# 09_Ethernet-RGMII.net
KiCad netlist of a schematic drawn in Altium Designer
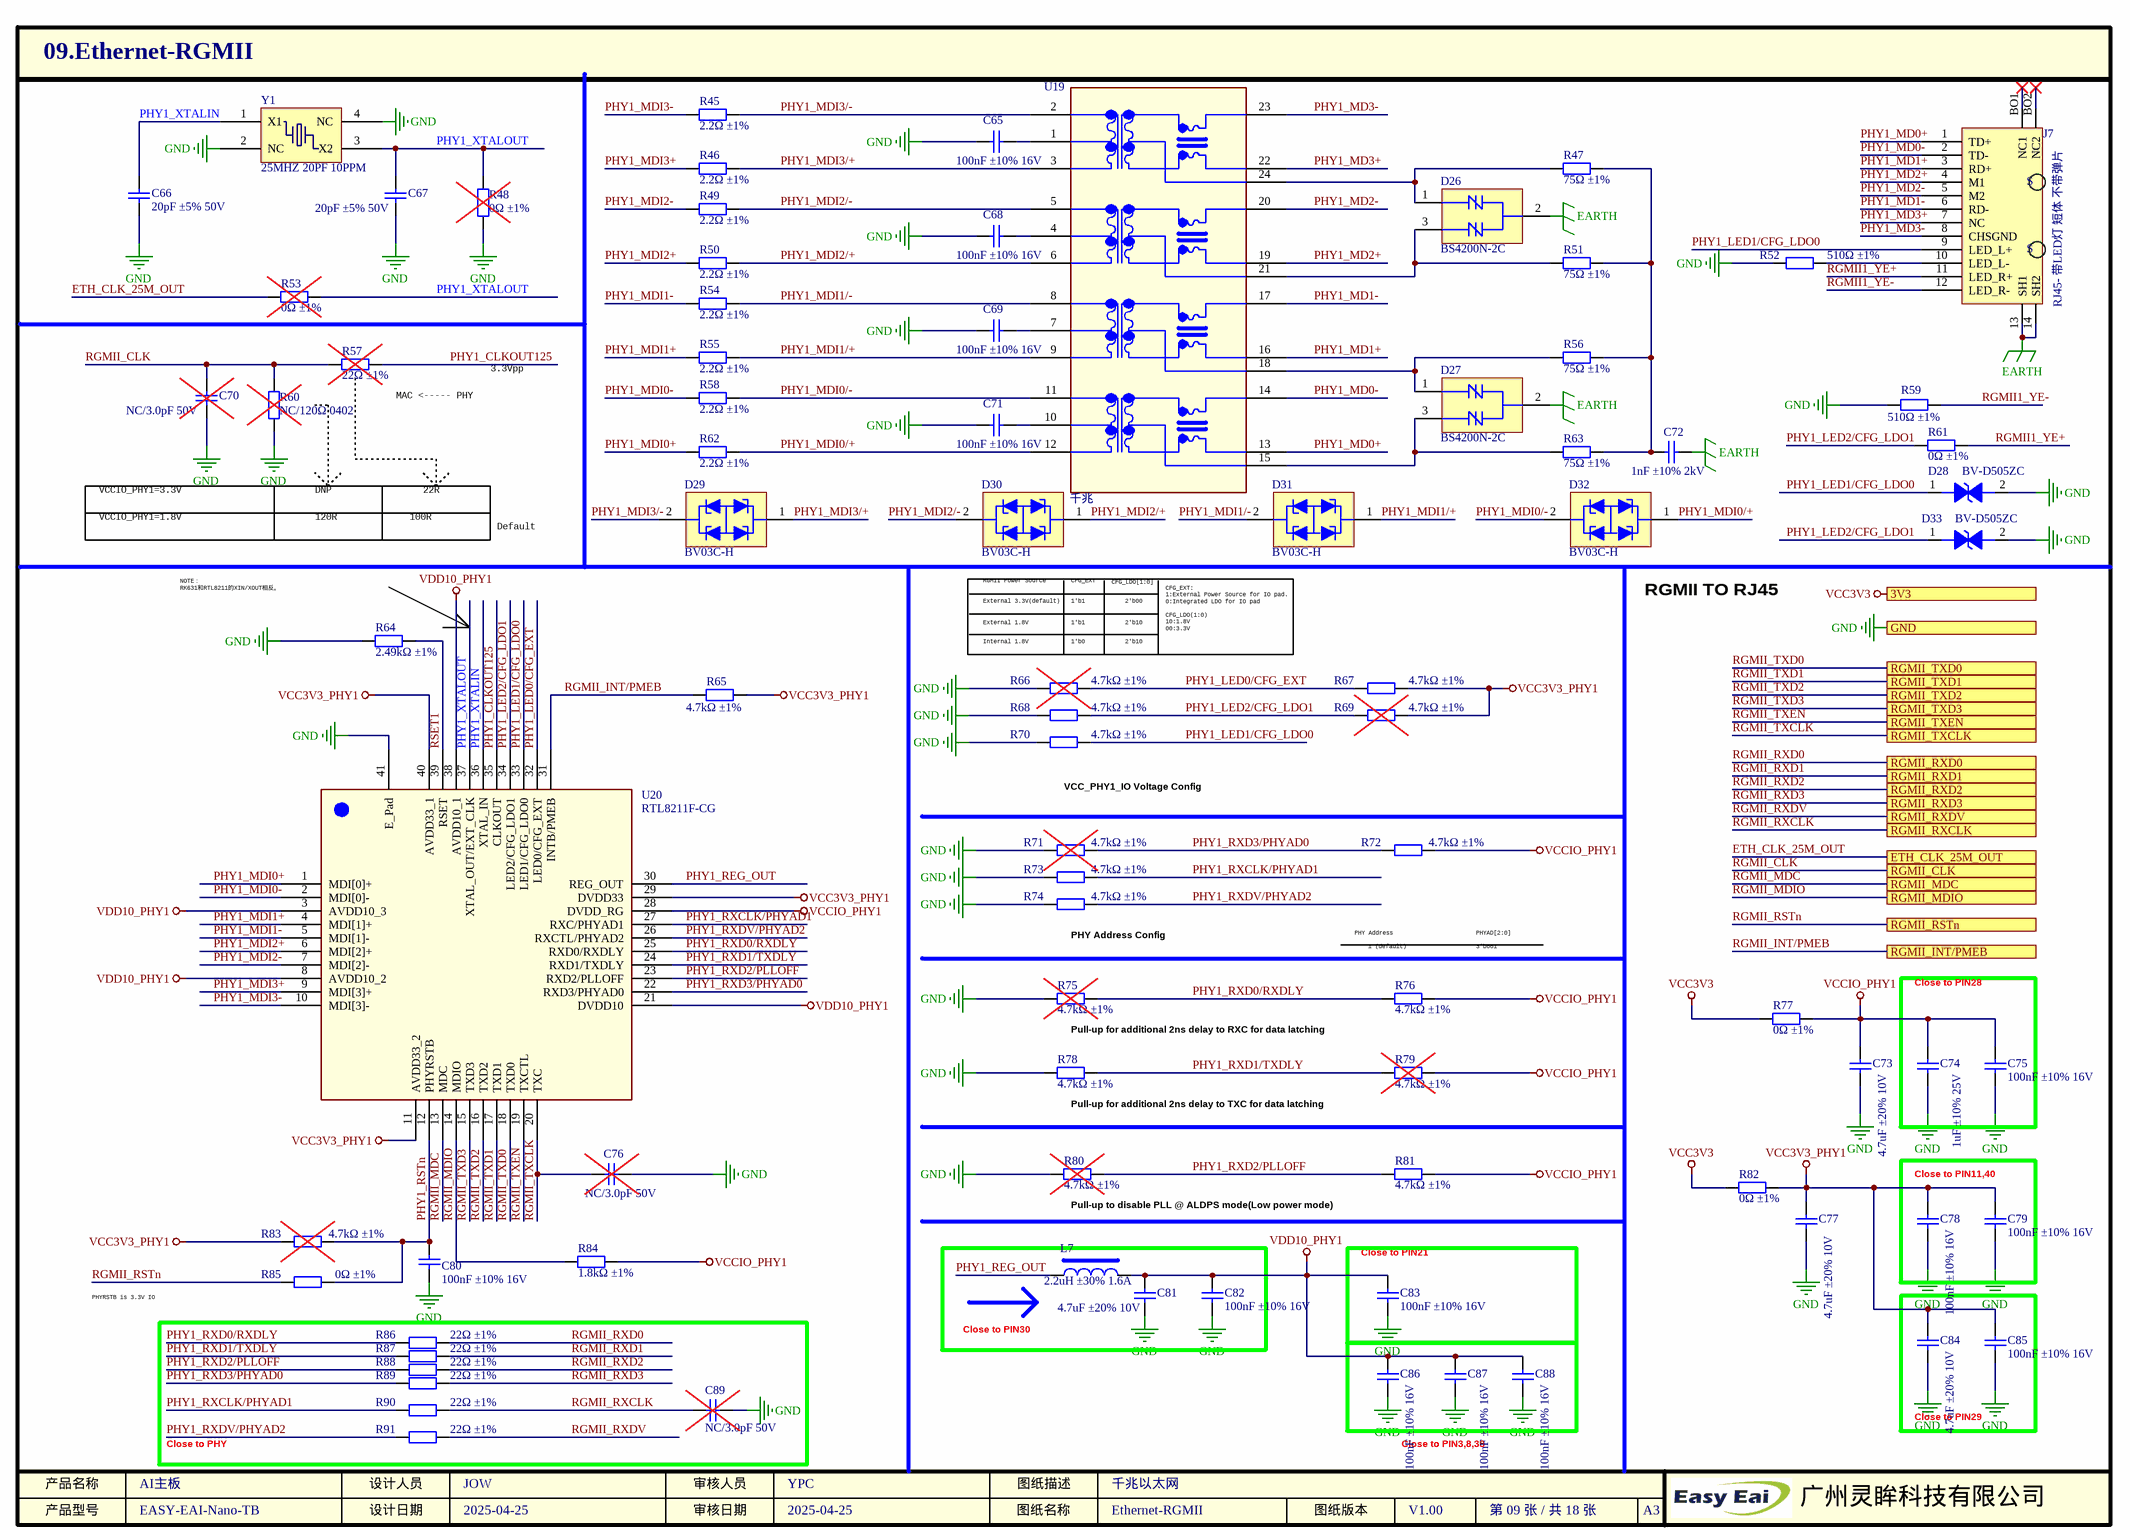
[diagram p0: 09.Ethernet-RGMII.SchDoc]

(export (version "E")
  (design (tool "Eeschema 10.0.6"))
  (components
    (comp (ref "C65")
      (value "CL05B104KO5NNNC")
      (footprint "0402_C")
      (description "SPZL000259")
      (fields (field (name "描述") "100nF ±10% 16V"))
      (libsource (lib "CAP_lexing") (part "0402 100nF ±10% 16V"))
    )
    (comp (ref "C66")
      (value "0402CG200J500NT")
      (footprint "0402_C")
      (description "SPZL000398")
      (fields (field (name "描述") "20pF ±5% 50V"))
      (libsource (lib "CAP_lexing") (part "0402 20pF ±5% 50V"))
    )
    (comp (ref "C67")
      (value "0402CG200J500NT")
      (footprint "0402_C")
      (description "SPZL000398")
      (fields (field (name "描述") "20pF ±5% 50V"))
      (libsource (lib "CAP_lexing") (part "0402 20pF ±5% 50V"))
    )
    (comp (ref "C68")
      (value "CL05B104KO5NNNC")
      (footprint "0402_C")
      (description "SPZL000259")
      (fields (field (name "描述") "100nF ±10% 16V"))
      (libsource (lib "CAP_lexing") (part "0402 100nF ±10% 16V"))
    )
    (comp (ref "C69")
      (value "CL05B104KO5NNNC")
      (footprint "0402_C")
      (description "SPZL000259")
      (fields (field (name "描述") "100nF ±10% 16V"))
      (libsource (lib "CAP_lexing") (part "0402 100nF ±10% 16V"))
    )
    (comp (ref "C70")
      (value "NC/3.0pF 50V")
      (footprint "0402_C")
      (description "贴片电容")
      (libsource (lib "Cap") (part "0402 2.0pF (2R0) 0.25pF 50V"))
    )
    (comp (ref "C71")
      (value "CL05B104KO5NNNC")
      (footprint "0402_C")
      (description "SPZL000259")
      (fields (field (name "描述") "100nF ±10% 16V"))
      (libsource (lib "CAP_lexing") (part "0402 100nF ±10% 16V"))
    )
    (comp (ref "C72")
      (value "CC1206KKX7RDBB102")
      (footprint "1206_C")
      (description "SPZL000332")
      (fields (field (name "描述") "1nF ±10% 2kV"))
      (libsource (lib "CAP_lexing") (part "1206 1nF ±10% 2kV"))
    )
    (comp (ref "C73")
      (value "CL05A475MP5NRNC")
      (footprint "0402_C")
      (description "SPZL000339")
      (fields (field (name "描述") "4.7uF ±20% 10V"))
      (libsource (lib "CAP_lexing") (part "0402 4.7uF ±20% 10V"))
    )
    (comp (ref "C74")
      (value "CL05A105KA5NQNC")
      (footprint "0402_C")
      (description "SPZL000337")
      (fields (field (name "描述") "1uF ±10% 25V"))
      (libsource (lib "CAP_lexing") (part "0402 1uF ±10% 25V"))
    )
    (comp (ref "C75")
      (value "CL05B104KO5NNNC")
      (footprint "0402_C")
      (description "SPZL000259")
      (fields (field (name "描述") "100nF ±10% 16V"))
      (libsource (lib "CAP_lexing") (part "0402 100nF ±10% 16V"))
    )
    (comp (ref "C76")
      (value "NC/3.0pF 50V")
      (footprint "0402_C")
      (description "贴片电容")
      (libsource (lib "Cap") (part "0402 2.0pF (2R0) 0.25pF 50V"))
    )
    (comp (ref "C77")
      (value "CL05A475MP5NRNC")
      (footprint "0402_C")
      (description "SPZL000339")
      (fields (field (name "描述") "4.7uF ±20% 10V"))
      (libsource (lib "CAP_lexing") (part "0402 4.7uF ±20% 10V"))
    )
    (comp (ref "C78")
      (value "CL05B104KO5NNNC")
      (footprint "0402_C")
      (description "SPZL000259")
      (fields (field (name "描述") "100nF ±10% 16V"))
      (libsource (lib "CAP_lexing") (part "0402 100nF ±10% 16V"))
    )
    (comp (ref "C79")
      (value "CL05B104KO5NNNC")
      (footprint "0402_C")
      (description "SPZL000259")
      (fields (field (name "描述") "100nF ±10% 16V"))
      (libsource (lib "CAP_lexing") (part "0402 100nF ±10% 16V"))
    )
    (comp (ref "C80")
      (value "CL05B104KO5NNNC")
      (footprint "0402_C")
      (description "SPZL000259")
      (fields (field (name "描述") "100nF ±10% 16V"))
      (libsource (lib "CAP_lexing") (part "0402 100nF ±10% 16V"))
    )
    (comp (ref "C81")
      (value "CL05A475MP5NRNC")
      (footprint "0402_C")
      (description "SPZL000339")
      (fields (field (name "描述") "4.7uF ±20% 10V"))
      (libsource (lib "CAP_lexing") (part "0402 4.7uF ±20% 10V"))
    )
    (comp (ref "C82")
      (value "CL05B104KO5NNNC")
      (footprint "0402_C")
      (description "SPZL000259")
      (fields (field (name "描述") "100nF ±10% 16V"))
      (libsource (lib "CAP_lexing") (part "0402 100nF ±10% 16V"))
    )
    (comp (ref "C83")
      (value "CL05B104KO5NNNC")
      (footprint "0402_C")
      (description "SPZL000259")
      (fields (field (name "描述") "100nF ±10% 16V"))
      (libsource (lib "CAP_lexing") (part "0402 100nF ±10% 16V"))
    )
    (comp (ref "C84")
      (value "CL05A475MP5NRNC")
      (footprint "0402_C")
      (description "SPZL000339")
      (fields (field (name "描述") "4.7uF ±20% 10V"))
      (libsource (lib "CAP_lexing") (part "0402 4.7uF ±20% 10V"))
    )
    (comp (ref "C85")
      (value "CL05B104KO5NNNC")
      (footprint "0402_C")
      (description "SPZL000259")
      (fields (field (name "描述") "100nF ±10% 16V"))
      (libsource (lib "CAP_lexing") (part "0402 100nF ±10% 16V"))
    )
    (comp (ref "C86")
      (value "CL05B104KO5NNNC")
      (footprint "0402_C")
      (description "SPZL000259")
      (fields (field (name "描述") "100nF ±10% 16V"))
      (libsource (lib "CAP_lexing") (part "0402 100nF ±10% 16V"))
    )
    (comp (ref "C87")
      (value "CL05B104KO5NNNC")
      (footprint "0402_C")
      (description "SPZL000259")
      (fields (field (name "描述") "100nF ±10% 16V"))
      (libsource (lib "CAP_lexing") (part "0402 100nF ±10% 16V"))
    )
    (comp (ref "C88")
      (value "CL05B104KO5NNNC")
      (footprint "0402_C")
      (description "SPZL000259")
      (fields (field (name "描述") "100nF ±10% 16V"))
      (libsource (lib "CAP_lexing") (part "0402 100nF ±10% 16V"))
    )
    (comp (ref "C89")
      (value "NC/3.0pF 50V")
      (footprint "0402_C")
      (description "贴片电容")
      (libsource (lib "Cap") (part "0402 2.0pF (2R0) 0.25pF 50V"))
    )
    (comp (ref "D26")
      (value "BS4200N-2C")
      (footprint "SMB-T_L5.4-W3.3-BI")
      (description "SPZL000612")
      (fields (field (name "型号") "BS4200N-2C"))
      (libsource (lib "ESD_lexing") (part "放电管 BS4200N-2C"))
    )
    (comp (ref "D27")
      (value "BS4200N-2C")
      (footprint "SMB-T_L5.4-W3.3-BI")
      (description "SPZL000612")
      (fields (field (name "型号") "BS4200N-2C"))
      (libsource (lib "ESD_lexing") (part "放电管 BS4200N-2C"))
    )
    (comp (ref "D28")
      (value "BV-D505ZC")
      (footprint "SOD-523")
      (description "SPZL000613")
      (fields (field (name "型号") "BV-D505ZC"))
      (libsource (lib "ESD_lexing") (part "ESD BV-D505ZC"))
    )
    (comp (ref "D29")
      (value "BV03C-H")
      (footprint "SOD-323")
      (description "SPZL000614")
      (fields (field (name "型号") "BV03C-H"))
      (libsource (lib "ESD_lexing") (part "ESD BV03C-H"))
    )
    (comp (ref "D30")
      (value "BV03C-H")
      (footprint "SOD-323")
      (description "SPZL000614")
      (fields (field (name "型号") "BV03C-H"))
      (libsource (lib "ESD_lexing") (part "ESD BV03C-H"))
    )
    (comp (ref "D31")
      (value "BV03C-H")
      (footprint "SOD-323")
      (description "SPZL000614")
      (fields (field (name "型号") "BV03C-H"))
      (libsource (lib "ESD_lexing") (part "ESD BV03C-H"))
    )
    (comp (ref "D32")
      (value "BV03C-H")
      (footprint "SOD-323")
      (description "SPZL000614")
      (fields (field (name "型号") "BV03C-H"))
      (libsource (lib "ESD_lexing") (part "ESD BV03C-H"))
    )
    (comp (ref "D33")
      (value "BV-D505ZC")
      (footprint "SOD-523")
      (description "SPZL000613")
      (fields (field (name "型号") "BV-D505ZC"))
      (libsource (lib "ESD_lexing") (part "ESD BV-D505ZC"))
    )
    (comp (ref "J7")
      (value "R-RJ45R08P-C000")
      (footprint "RJ45/LED-1575X1626X1310")
      (description "SPZL000140")
      (fields (field (name "描述") "RJ45- 带LED灯 短体 不带弹片"))
      (libsource (lib "EVBoard-RK3562") (part "RJ45- 带LED灯 短体 不带弹片"))
    )
    (comp (ref "L7")
      (value "SWPA3015S2R2NT")
      (footprint "IND-SMD_L3.0-W3.0")
      (description "SPZL000721")
      (fields (field (name "描述") "2.2uH ±30% 1.6A"))
      (libsource (lib "Inductor_lexing") (part "2.2uH ±30% 1.6A"))
    )
    (comp (ref "R45")
      (value "0402WGF220KTCE")
      (footprint "0402_R")
      (description "SPZL000327")
      (fields (field (name "描述") "2.2Ω ±1%"))
      (libsource (lib "RES_lexing") (part "0402 2.2Ω ±1%"))
    )
    (comp (ref "R46")
      (value "0402WGF220KTCE")
      (footprint "0402_R")
      (description "SPZL000327")
      (fields (field (name "描述") "2.2Ω ±1%"))
      (libsource (lib "RES_lexing") (part "0402 2.2Ω ±1%"))
    )
    (comp (ref "R47")
      (value "RS-05K75R0FT")
      (footprint "0805_R")
      (description "SPZL000353")
      (fields (field (name "描述") "75Ω ±1%"))
      (libsource (lib "RES_lexing") (part "0805 75Ω ±1%"))
    )
    (comp (ref "R48")
      (value "NC/0402WGF0000TCE")
      (footprint "0402_R")
      (description "SPZL000276")
      (fields (field (name "描述") "0Ω ±1%"))
      (libsource (lib "RES_lexing") (part "0402 0Ω ±1%"))
    )
    (comp (ref "R49")
      (value "0402WGF220KTCE")
      (footprint "0402_R")
      (description "SPZL000327")
      (fields (field (name "描述") "2.2Ω ±1%"))
      (libsource (lib "RES_lexing") (part "0402 2.2Ω ±1%"))
    )
    (comp (ref "R50")
      (value "0402WGF220KTCE")
      (footprint "0402_R")
      (description "SPZL000327")
      (fields (field (name "描述") "2.2Ω ±1%"))
      (libsource (lib "RES_lexing") (part "0402 2.2Ω ±1%"))
    )
    (comp (ref "R51")
      (value "RS-05K75R0FT")
      (footprint "0805_R")
      (description "SPZL000353")
      (fields (field (name "描述") "75Ω ±1%"))
      (libsource (lib "RES_lexing") (part "0805 75Ω ±1%"))
    )
    (comp (ref "R52")
      (value "0402WGF5100TCE")
      (footprint "0402_R")
      (description "SPZL000335")
      (fields (field (name "描述") "510Ω ±1%"))
      (libsource (lib "RES_lexing") (part "0402 510Ω ±1%"))
    )
    (comp (ref "R53")
      (value "NC/0402WGF0000TCE")
      (footprint "0402_R")
      (description "SPZL000276")
      (fields (field (name "描述") "0Ω ±1%"))
      (libsource (lib "") (part "0402 0Ω ±1%_2"))
    )
    (comp (ref "R54")
      (value "0402WGF220KTCE")
      (footprint "0402_R")
      (description "SPZL000327")
      (fields (field (name "描述") "2.2Ω ±1%"))
      (libsource (lib "RES_lexing") (part "0402 2.2Ω ±1%"))
    )
    (comp (ref "R55")
      (value "0402WGF220KTCE")
      (footprint "0402_R")
      (description "SPZL000327")
      (fields (field (name "描述") "2.2Ω ±1%"))
      (libsource (lib "RES_lexing") (part "0402 2.2Ω ±1%"))
    )
    (comp (ref "R56")
      (value "RS-05K75R0FT")
      (footprint "0805_R")
      (description "SPZL000353")
      (fields (field (name "描述") "75Ω ±1%"))
      (libsource (lib "RES_lexing") (part "0805 75Ω ±1%"))
    )
    (comp (ref "R57")
      (value "0402WGF220JTCE")
      (footprint "0402_R")
      (description "SPZL000279")
      (fields (field (name "描述") "22Ω ±1%"))
      (libsource (lib "RES_lexing") (part "0402 22Ω ±1%"))
    )
    (comp (ref "R58")
      (value "0402WGF220KTCE")
      (footprint "0402_R")
      (description "SPZL000327")
      (fields (field (name "描述") "2.2Ω ±1%"))
      (libsource (lib "RES_lexing") (part "0402 2.2Ω ±1%"))
    )
    (comp (ref "R59")
      (value "0402WGF5100TCE")
      (footprint "0402_R")
      (description "SPZL000335")
      (fields (field (name "描述") "510Ω ±1%"))
      (libsource (lib "RES_lexing") (part "0402 510Ω ±1%"))
    )
    (comp (ref "R60")
      (value "NC/120Ω 0402")
      (footprint "0402_R")
      (description "贴片电阻")
      (libsource (lib "RES") (part "0402 120Ω (1200) 1%"))
    )
    (comp (ref "R61")
      (value "0402WGF0000TCE")
      (footprint "0402_R")
      (description "SPZL000276")
      (fields (field (name "描述") "0Ω ±1%"))
      (libsource (lib "") (part "0402 0Ω ±1%_1"))
    )
    (comp (ref "R62")
      (value "0402WGF220KTCE")
      (footprint "0402_R")
      (description "SPZL000327")
      (fields (field (name "描述") "2.2Ω ±1%"))
      (libsource (lib "RES_lexing") (part "0402 2.2Ω ±1%"))
    )
    (comp (ref "R63")
      (value "RS-05K75R0FT")
      (footprint "0805_R")
      (description "SPZL000353")
      (fields (field (name "描述") "75Ω ±1%"))
      (libsource (lib "RES_lexing") (part "0805 75Ω ±1%"))
    )
    (comp (ref "R64")
      (value "AC0402FR-072K49L")
      (footprint "0402_R")
      (description "SPZL000354")
      (fields (field (name "描述") "2.49kΩ ±1%"))
      (libsource (lib "RES_lexing") (part "0402 2.49kΩ ±1%"))
    )
    (comp (ref "R65")
      (value "0402WGF4701TCE")
      (footprint "0402_R")
      (description "SPZL000280")
      (fields (field (name "描述") "4.7kΩ ±1%"))
      (libsource (lib "RES_lexing") (part "0402 4.7kΩ ±1%"))
    )
    (comp (ref "R66")
      (value "NC/0402WGF4701TCE")
      (footprint "0402_R")
      (description "SPZL000280")
      (fields (field (name "描述") "4.7kΩ ±1%"))
      (libsource (lib "RES_lexing") (part "0402 4.7kΩ ±1%"))
    )
    (comp (ref "R67")
      (value "0402WGF4701TCE")
      (footprint "0402_R")
      (description "SPZL000280")
      (fields (field (name "描述") "4.7kΩ ±1%"))
      (libsource (lib "RES_lexing") (part "0402 4.7kΩ ±1%"))
    )
    (comp (ref "R68")
      (value "0402WGF4701TCE")
      (footprint "0402_R")
      (description "SPZL000280")
      (fields (field (name "描述") "4.7kΩ ±1%"))
      (libsource (lib "RES_lexing") (part "0402 4.7kΩ ±1%"))
    )
    (comp (ref "R69")
      (value "NC/0402WGF4701TCE")
      (footprint "0402_R")
      (description "SPZL000280")
      (fields (field (name "描述") "4.7kΩ ±1%"))
      (libsource (lib "RES_lexing") (part "0402 4.7kΩ ±1%"))
    )
    (comp (ref "R70")
      (value "0402WGF4701TCE")
      (footprint "0402_R")
      (description "SPZL000280")
      (fields (field (name "描述") "4.7kΩ ±1%"))
      (libsource (lib "RES_lexing") (part "0402 4.7kΩ ±1%"))
    )
    (comp (ref "R71")
      (value "NC/0402WGF4701TCE")
      (footprint "0402_R")
      (description "SPZL000280")
      (fields (field (name "描述") "4.7kΩ ±1%"))
      (libsource (lib "RES_lexing") (part "0402 4.7kΩ ±1%"))
    )
    (comp (ref "R72")
      (value "0402WGF4701TCE")
      (footprint "0402_R")
      (description "SPZL000280")
      (fields (field (name "描述") "4.7kΩ ±1%"))
      (libsource (lib "RES_lexing") (part "0402 4.7kΩ ±1%"))
    )
    (comp (ref "R73")
      (value "0402WGF4701TCE")
      (footprint "0402_R")
      (description "SPZL000280")
      (fields (field (name "描述") "4.7kΩ ±1%"))
      (libsource (lib "RES_lexing") (part "0402 4.7kΩ ±1%"))
    )
    (comp (ref "R74")
      (value "0402WGF4701TCE")
      (footprint "0402_R")
      (description "SPZL000280")
      (fields (field (name "描述") "4.7kΩ ±1%"))
      (libsource (lib "RES_lexing") (part "0402 4.7kΩ ±1%"))
    )
    (comp (ref "R75")
      (value "NC/0402WGF4701TCE")
      (footprint "0402_R")
      (description "SPZL000280")
      (fields (field (name "描述") "4.7kΩ ±1%"))
      (libsource (lib "RES_lexing") (part "0402 4.7kΩ ±1%"))
    )
    (comp (ref "R76")
      (value "0402WGF4701TCE")
      (footprint "0402_R")
      (description "SPZL000280")
      (fields (field (name "描述") "4.7kΩ ±1%"))
      (libsource (lib "RES_lexing") (part "0402 4.7kΩ ±1%"))
    )
    (comp (ref "R77")
      (value "0402WGF0000TCE")
      (footprint "0402_R")
      (description "SPZL000276")
      (fields (field (name "描述") "0Ω ±1%"))
      (libsource (lib "") (part "0402 0Ω ±1%_1"))
    )
    (comp (ref "R78")
      (value "0402WGF4701TCE")
      (footprint "0402_R")
      (description "SPZL000280")
      (fields (field (name "描述") "4.7kΩ ±1%"))
      (libsource (lib "RES_lexing") (part "0402 4.7kΩ ±1%"))
    )
    (comp (ref "R79")
      (value "NC/0402WGF4701TCE")
      (footprint "0402_R")
      (description "SPZL000280")
      (fields (field (name "描述") "4.7kΩ ±1%"))
      (libsource (lib "RES_lexing") (part "0402 4.7kΩ ±1%"))
    )
    (comp (ref "R80")
      (value "NC/0402WGF4701TCE")
      (footprint "0402_R")
      (description "SPZL000280")
      (fields (field (name "描述") "4.7kΩ ±1%"))
      (libsource (lib "RES_lexing") (part "0402 4.7kΩ ±1%"))
    )
    (comp (ref "R81")
      (value "0402WGF4701TCE")
      (footprint "0402_R")
      (description "SPZL000280")
      (fields (field (name "描述") "4.7kΩ ±1%"))
      (libsource (lib "RES_lexing") (part "0402 4.7kΩ ±1%"))
    )
    (comp (ref "R82")
      (value "0402WGF0000TCE")
      (footprint "0402_R")
      (description "SPZL000276")
      (fields (field (name "描述") "0Ω ±1%"))
      (libsource (lib "") (part "0402 0Ω ±1%_1"))
    )
    (comp (ref "R83")
      (value "NC/0402WGF4701TCE")
      (footprint "0402_R")
      (description "SPZL000280")
      (fields (field (name "描述") "4.7kΩ ±1%"))
      (libsource (lib "RES_lexing") (part "0402 4.7kΩ ±1%"))
    )
    (comp (ref "R84")
      (value "0402WGF1801TCE")
      (footprint "0402_R")
      (description "SPZL000899")
      (fields (field (name "描述") "1.8kΩ ±1%"))
      (libsource (lib "RES_lexing") (part "0402 1.8kΩ ±1%"))
    )
    (comp (ref "R85")
      (value "0402WGF0000TCE")
      (footprint "0402_R")
      (description "SPZL000276")
      (fields (field (name "描述") "0Ω ±1%"))
      (libsource (lib "") (part "0402 0Ω ±1%_1"))
    )
    (comp (ref "R86")
      (value "0402WGF220JTCE")
      (footprint "0402_R")
      (description "SPZL000279")
      (fields (field (name "描述") "22Ω ±1%"))
      (libsource (lib "RES_lexing") (part "0402 22Ω ±1%"))
    )
    (comp (ref "R87")
      (value "0402WGF220JTCE")
      (footprint "0402_R")
      (description "SPZL000279")
      (fields (field (name "描述") "22Ω ±1%"))
      (libsource (lib "RES_lexing") (part "0402 22Ω ±1%"))
    )
    (comp (ref "R88")
      (value "0402WGF220JTCE")
      (footprint "0402_R")
      (description "SPZL000279")
      (fields (field (name "描述") "22Ω ±1%"))
      (libsource (lib "RES_lexing") (part "0402 22Ω ±1%"))
    )
    (comp (ref "R89")
      (value "0402WGF220JTCE")
      (footprint "0402_R")
      (description "SPZL000279")
      (fields (field (name "描述") "22Ω ±1%"))
      (libsource (lib "RES_lexing") (part "0402 22Ω ±1%"))
    )
    (comp (ref "R90")
      (value "0402WGF220JTCE")
      (footprint "0402_R")
      (description "SPZL000279")
      (fields (field (name "描述") "22Ω ±1%"))
      (libsource (lib "RES_lexing") (part "0402 22Ω ±1%"))
    )
    (comp (ref "R91")
      (value "0402WGF220JTCE")
      (footprint "0402_R")
      (description "SPZL000279")
      (fields (field (name "描述") "22Ω ±1%"))
      (libsource (lib "RES_lexing") (part "0402 22Ω ±1%"))
    )
    (comp (ref "U19")
      (value "G2401CE")
      (footprint "SMD-24_L15.1-W7.1-P1.00-LS10.0-BL")
      (description "SPZL000720")
      (fields (field (name "描述") "千兆"))
      (libsource (lib "ESD_lexing") (part "网络变压器 G2401CE"))
    )
    (comp (ref "U20")
      (value "RTL8211F-CG")
      (footprint "QFN40P500X500X90_HS-41N")
      (description "SPZL000719")
      (fields (field (name "型号") "RTL8211F-CG"))
      (libsource (lib "IC_lexing") (part "RTL8211F-CG"))
    )
    (comp (ref "Y1")
      (value "X322525MSB4SI")
      (footprint "SMD-3225_4P")
      (description "SPZL000475")
      (fields (field (name "描述") "25MHZ 20PF 10PPM"))
      (libsource (lib "XTAL_lexing") (part "25MHZ 20PF 10PPM"))
    )
  )
  (nets
    (net (code "1") (name "/ETH_CLK_25M_OUT") (class "Default")
      (node (ref "R53") (pin "2") (pinfunction "2_2") (pintype "passive"))
    )
    (net (code "2") (name "/PHY1_CLKOUT125") (class "Default")
      (node (ref "R57") (pin "2") (pinfunction "2_2") (pintype "passive"))
      (node (ref "U20") (pin "35") (pinfunction "CLKOUT_35") (pintype "passive"))
    )
    (net (code "3") (name "/PHY1_LED0{slash}CFG_EXT") (class "Default")
      (node (ref "R66") (pin "2") (pinfunction "2_2") (pintype "passive"))
      (node (ref "R67") (pin "1") (pinfunction "1_1") (pintype "passive"))
      (node (ref "U20") (pin "32") (pinfunction "LED0/CFG_EXT_32") (pintype "passive"))
    )
    (net (code "4") (name "/PHY1_LED1{slash}CFG_LDO0") (class "Default")
      (node (ref "D28") (pin "1") (pinfunction "1_1") (pintype "passive"))
      (node (ref "J7") (pin "9") (pinfunction "LED_L+_9") (pintype "passive"))
      (node (ref "R70") (pin "2") (pinfunction "2_2") (pintype "passive"))
      (node (ref "U20") (pin "33") (pinfunction "LED1/CFG_LDO0_33") (pintype "passive"))
    )
    (net (code "5") (name "/PHY1_LED2{slash}CFG_LDO1") (class "Default")
      (node (ref "D33") (pin "1") (pinfunction "1_1") (pintype "passive"))
      (node (ref "R61") (pin "1") (pinfunction "1_1") (pintype "passive"))
      (node (ref "R68") (pin "2") (pinfunction "2_2") (pintype "passive"))
      (node (ref "R69") (pin "1") (pinfunction "1_1") (pintype "passive"))
      (node (ref "U20") (pin "34") (pinfunction "LED2/CFG_LDO1_34") (pintype "passive"))
    )
    (net (code "6") (name "/PHY1_MD0+") (class "Default")
      (node (ref "J7") (pin "1") (pinfunction "TD+_1") (pintype "passive"))
      (node (ref "U19") (pin "13") (pinfunction "13_13") (pintype "passive"))
    )
    (net (code "7") (name "/PHY1_MD0-") (class "Default")
      (node (ref "J7") (pin "2") (pinfunction "TD-_2") (pintype "passive"))
      (node (ref "U19") (pin "14") (pinfunction "14_14") (pintype "passive"))
    )
    (net (code "8") (name "/PHY1_MD1+") (class "Default")
      (node (ref "J7") (pin "3") (pinfunction "RD+_3") (pintype "passive"))
      (node (ref "U19") (pin "16") (pinfunction "16_16") (pintype "passive"))
    )
    (net (code "9") (name "/PHY1_MD1-") (class "Default")
      (node (ref "J7") (pin "6") (pinfunction "RD-_6") (pintype "passive"))
      (node (ref "U19") (pin "17") (pinfunction "17_17") (pintype "passive"))
    )
    (net (code "10") (name "/PHY1_MD2+") (class "Default")
      (node (ref "J7") (pin "4") (pinfunction "M1_4") (pintype "passive"))
      (node (ref "U19") (pin "19") (pinfunction "19_19") (pintype "passive"))
    )
    (net (code "11") (name "/PHY1_MD2-") (class "Default")
      (node (ref "J7") (pin "5") (pinfunction "M2_5") (pintype "passive"))
      (node (ref "U19") (pin "20") (pinfunction "20_20") (pintype "passive"))
    )
    (net (code "12") (name "/PHY1_MD3+") (class "Default")
      (node (ref "J7") (pin "7") (pinfunction "NC_7") (pintype "passive"))
      (node (ref "U19") (pin "22") (pinfunction "22_22") (pintype "passive"))
    )
    (net (code "13") (name "/PHY1_MD3-") (class "Default")
      (node (ref "J7") (pin "8") (pinfunction "CHSGND_8") (pintype "passive"))
      (node (ref "U19") (pin "23") (pinfunction "23_23") (pintype "passive"))
    )
    (net (code "14") (name "/PHY1_MDI0+") (class "Default")
      (node (ref "R62") (pin "1") (pinfunction "1_1") (pintype "passive"))
      (node (ref "U20") (pin "1") (pinfunction "MDI[0]+_1") (pintype "passive"))
    )
    (net (code "15") (name "/PHY1_MDI0-") (class "Default")
      (node (ref "R58") (pin "1") (pinfunction "1_1") (pintype "passive"))
      (node (ref "U20") (pin "2") (pinfunction "MDI[0]-_2") (pintype "passive"))
    )
    (net (code "16") (name "/PHY1_MDI0{slash}+") (class "Default")
      (node (ref "D32") (pin "1") (pintype "passive"))
      (node (ref "R62") (pin "2") (pinfunction "2_2") (pintype "passive"))
      (node (ref "U19") (pin "12") (pinfunction "12_12") (pintype "passive"))
    )
    (net (code "17") (name "/PHY1_MDI0{slash}-") (class "Default")
      (node (ref "D32") (pin "2") (pintype "passive"))
      (node (ref "R58") (pin "2") (pinfunction "2_2") (pintype "passive"))
      (node (ref "U19") (pin "11") (pinfunction "11_11") (pintype "passive"))
    )
    (net (code "18") (name "/PHY1_MDI1+") (class "Default")
      (node (ref "R55") (pin "1") (pinfunction "1_1") (pintype "passive"))
      (node (ref "U20") (pin "4") (pinfunction "MDI[1]+_4") (pintype "passive"))
    )
    (net (code "19") (name "/PHY1_MDI1-") (class "Default")
      (node (ref "R54") (pin "1") (pinfunction "1_1") (pintype "passive"))
      (node (ref "U20") (pin "5") (pinfunction "MDI[1]-_5") (pintype "passive"))
    )
    (net (code "20") (name "/PHY1_MDI1{slash}+") (class "Default")
      (node (ref "D31") (pin "1") (pintype "passive"))
      (node (ref "R55") (pin "2") (pinfunction "2_2") (pintype "passive"))
      (node (ref "U19") (pin "9") (pinfunction "9_9") (pintype "passive"))
    )
    (net (code "21") (name "/PHY1_MDI1{slash}-") (class "Default")
      (node (ref "D31") (pin "2") (pintype "passive"))
      (node (ref "R54") (pin "2") (pinfunction "2_2") (pintype "passive"))
      (node (ref "U19") (pin "8") (pinfunction "8_8") (pintype "passive"))
    )
    (net (code "22") (name "/PHY1_MDI2+") (class "Default")
      (node (ref "R50") (pin "1") (pinfunction "1_1") (pintype "passive"))
      (node (ref "U20") (pin "6") (pinfunction "MDI[2]+_6") (pintype "passive"))
    )
    (net (code "23") (name "/PHY1_MDI2-") (class "Default")
      (node (ref "R49") (pin "1") (pinfunction "1_1") (pintype "passive"))
      (node (ref "U20") (pin "7") (pinfunction "MDI[2]-_7") (pintype "passive"))
    )
    (net (code "24") (name "/PHY1_MDI2{slash}+") (class "Default")
      (node (ref "D30") (pin "1") (pintype "passive"))
      (node (ref "R50") (pin "2") (pinfunction "2_2") (pintype "passive"))
      (node (ref "U19") (pin "6") (pinfunction "6_6") (pintype "passive"))
    )
    (net (code "25") (name "/PHY1_MDI2{slash}-") (class "Default")
      (node (ref "D30") (pin "2") (pintype "passive"))
      (node (ref "R49") (pin "2") (pinfunction "2_2") (pintype "passive"))
      (node (ref "U19") (pin "5") (pinfunction "5_5") (pintype "passive"))
    )
    (net (code "26") (name "/PHY1_MDI3+") (class "Default")
      (node (ref "R46") (pin "1") (pinfunction "1_1") (pintype "passive"))
      (node (ref "U20") (pin "9") (pinfunction "MDI[3]+_9") (pintype "passive"))
    )
    (net (code "27") (name "/PHY1_MDI3-") (class "Default")
      (node (ref "R45") (pin "1") (pinfunction "1_1") (pintype "passive"))
      (node (ref "U20") (pin "10") (pinfunction "MDI[3]-_10") (pintype "passive"))
    )
    (net (code "28") (name "/PHY1_MDI3{slash}+") (class "Default")
      (node (ref "D29") (pin "1") (pintype "passive"))
      (node (ref "R46") (pin "2") (pinfunction "2_2") (pintype "passive"))
      (node (ref "U19") (pin "3") (pinfunction "3_3") (pintype "passive"))
    )
    (net (code "29") (name "/PHY1_MDI3{slash}-") (class "Default")
      (node (ref "D29") (pin "2") (pintype "passive"))
      (node (ref "R45") (pin "2") (pinfunction "2_2") (pintype "passive"))
      (node (ref "U19") (pin "2") (pinfunction "2_2") (pintype "passive"))
    )
    (net (code "30") (name "/PHY1_REG_OUT") (class "Default")
      (node (ref "L7") (pin "1") (pinfunction "1_1") (pintype "passive"))
      (node (ref "U20") (pin "30") (pinfunction "REG_OUT_30") (pintype "passive"))
    )
    (net (code "31") (name "/PHY1_RSTn") (class "Default")
      (node (ref "C80") (pin "2") (pinfunction "2_2") (pintype "passive"))
      (node (ref "R83") (pin "2") (pinfunction "2_2") (pintype "passive"))
      (node (ref "R85") (pin "2") (pinfunction "2_2") (pintype "passive"))
      (node (ref "U20") (pin "12") (pinfunction "PHYRSTB_12") (pintype "passive"))
    )
    (net (code "32") (name "/PHY1_RXCLK{slash}PHYAD1") (class "Default")
      (node (ref "R73") (pin "2") (pinfunction "2_2") (pintype "passive"))
      (node (ref "R90") (pin "1") (pinfunction "1_1") (pintype "passive"))
      (node (ref "U20") (pin "27") (pinfunction "RXC/PHYAD1_27") (pintype "passive"))
    )
    (net (code "33") (name "/PHY1_RXD0{slash}RXDLY") (class "Default")
      (node (ref "R75") (pin "2") (pinfunction "2_2") (pintype "passive"))
      (node (ref "R76") (pin "1") (pinfunction "1_1") (pintype "passive"))
      (node (ref "R86") (pin "1") (pinfunction "1_1") (pintype "passive"))
      (node (ref "U20") (pin "25") (pinfunction "RXD0/RXDLY_25") (pintype "passive"))
    )
    (net (code "34") (name "/PHY1_RXD1{slash}TXDLY") (class "Default")
      (node (ref "R78") (pin "2") (pinfunction "2_2") (pintype "passive"))
      (node (ref "R79") (pin "1") (pinfunction "1_1") (pintype "passive"))
      (node (ref "R87") (pin "1") (pinfunction "1_1") (pintype "passive"))
      (node (ref "U20") (pin "24") (pinfunction "RXD1/TXDLY_24") (pintype "passive"))
    )
    (net (code "35") (name "/PHY1_RXD2{slash}PLLOFF") (class "Default")
      (node (ref "R80") (pin "2") (pinfunction "2_2") (pintype "passive"))
      (node (ref "R81") (pin "1") (pinfunction "1_1") (pintype "passive"))
      (node (ref "R88") (pin "1") (pinfunction "1_1") (pintype "passive"))
      (node (ref "U20") (pin "23") (pinfunction "RXD2/PLLOFF_23") (pintype "passive"))
    )
    (net (code "36") (name "/PHY1_RXD3{slash}PHYAD0") (class "Default")
      (node (ref "R71") (pin "2") (pinfunction "2_2") (pintype "passive"))
      (node (ref "R72") (pin "1") (pinfunction "1_1") (pintype "passive"))
      (node (ref "R89") (pin "1") (pinfunction "1_1") (pintype "passive"))
      (node (ref "U20") (pin "22") (pinfunction "RXD3/PHYAD0_22") (pintype "passive"))
    )
    (net (code "37") (name "/PHY1_RXDV{slash}PHYAD2") (class "Default")
      (node (ref "R74") (pin "2") (pinfunction "2_2") (pintype "passive"))
      (node (ref "R91") (pin "1") (pinfunction "1_1") (pintype "passive"))
      (node (ref "U20") (pin "26") (pinfunction "RXCTL/PHYAD2_26") (pintype "passive"))
    )
    (net (code "38") (name "/PHY1_XTALIN") (class "Default")
      (node (ref "C66") (pin "2") (pinfunction "2_2") (pintype "passive"))
      (node (ref "U20") (pin "36") (pinfunction "XTAL_IN_36") (pintype "passive"))
      (node (ref "Y1") (pin "1") (pinfunction "X1_1") (pintype "passive"))
    )
    (net (code "39") (name "/PHY1_XTALOUT") (class "Default")
      (node (ref "C67") (pin "2") (pinfunction "2_2") (pintype "passive"))
      (node (ref "R48") (pin "2") (pinfunction "2_2") (pintype "passive"))
      (node (ref "R53") (pin "1") (pinfunction "1_1") (pintype "passive"))
      (node (ref "U20") (pin "37") (pinfunction "XTAL_OUT/EXT_CLK_37") (pintype "passive"))
      (node (ref "Y1") (pin "3") (pinfunction "X2_3") (pintype "passive"))
    )
    (net (code "40") (name "/RGMII1_YE+") (class "Default")
      (node (ref "J7") (pin "11") (pinfunction "LED_R+_11") (pintype "passive"))
      (node (ref "R61") (pin "2") (pinfunction "2_2") (pintype "passive"))
    )
    (net (code "41") (name "/RGMII1_YE-") (class "Default")
      (node (ref "J7") (pin "12") (pinfunction "LED_R-_12") (pintype "passive"))
      (node (ref "R59") (pin "2") (pinfunction "2_2") (pintype "passive"))
    )
    (net (code "42") (name "/RGMII_CLK") (class "Default")
      (node (ref "C70") (pin "2") (pinfunction "2_2") (pintype "passive"))
      (node (ref "R57") (pin "1") (pinfunction "1_1") (pintype "passive"))
      (node (ref "R60") (pin "2") (pinfunction "2_2") (pintype "passive"))
    )
    (net (code "43") (name "/RGMII_INT{slash}PMEB") (class "Default")
      (node (ref "R65") (pin "1") (pinfunction "1_1") (pintype "passive"))
      (node (ref "U20") (pin "31") (pinfunction "INTB/PMEB_31") (pintype "passive"))
    )
    (net (code "44") (name "/RGMII_MDC") (class "Default")
      (node (ref "U20") (pin "13") (pinfunction "MDC_13") (pintype "passive"))
    )
    (net (code "45") (name "/RGMII_MDIO") (class "Default")
      (node (ref "R84") (pin "1") (pinfunction "1_1") (pintype "passive"))
      (node (ref "U20") (pin "14") (pinfunction "MDIO_14") (pintype "passive"))
    )
    (net (code "46") (name "/RGMII_RSTn") (class "Default")
      (node (ref "R85") (pin "1") (pinfunction "1_1") (pintype "passive"))
    )
    (net (code "47") (name "/RGMII_RXCLK") (class "Default")
      (node (ref "C89") (pin "2") (pinfunction "2_2") (pintype "passive"))
      (node (ref "R90") (pin "2") (pinfunction "2_2") (pintype "passive"))
    )
    (net (code "48") (name "/RGMII_RXD0") (class "Default")
      (node (ref "R86") (pin "2") (pinfunction "2_2") (pintype "passive"))
    )
    (net (code "49") (name "/RGMII_RXD1") (class "Default")
      (node (ref "R87") (pin "2") (pinfunction "2_2") (pintype "passive"))
    )
    (net (code "50") (name "/RGMII_RXD2") (class "Default")
      (node (ref "R88") (pin "2") (pinfunction "2_2") (pintype "passive"))
    )
    (net (code "51") (name "/RGMII_RXD3") (class "Default")
      (node (ref "R89") (pin "2") (pinfunction "2_2") (pintype "passive"))
    )
    (net (code "52") (name "/RGMII_RXDV") (class "Default")
      (node (ref "R91") (pin "2") (pinfunction "2_2") (pintype "passive"))
    )
    (net (code "53") (name "/RGMII_TXCLK") (class "Default")
      (node (ref "C76") (pin "1") (pinfunction "1_1") (pintype "passive"))
      (node (ref "U20") (pin "20") (pinfunction "TXC_20") (pintype "passive"))
    )
    (net (code "54") (name "/RGMII_TXD0") (class "Default")
      (node (ref "U20") (pin "18") (pinfunction "TXD0_18") (pintype "passive"))
    )
    (net (code "55") (name "/RGMII_TXD1") (class "Default")
      (node (ref "U20") (pin "17") (pinfunction "TXD1_17") (pintype "passive"))
    )
    (net (code "56") (name "/RGMII_TXD2") (class "Default")
      (node (ref "U20") (pin "16") (pinfunction "TXD2_16") (pintype "passive"))
    )
    (net (code "57") (name "/RGMII_TXD3") (class "Default")
      (node (ref "U20") (pin "15") (pinfunction "TXD3_15") (pintype "passive"))
    )
    (net (code "58") (name "/RGMII_TXEN") (class "Default")
      (node (ref "U20") (pin "19") (pinfunction "TXCTL_19") (pintype "passive"))
    )
    (net (code "59") (name "/RSET1") (class "Default")
      (node (ref "R64") (pin "2") (pinfunction "2_2") (pintype "passive"))
      (node (ref "U20") (pin "39") (pinfunction "RSET_39") (pintype "passive"))
    )
    (net (code "60") (name "EARTH") (class "Default")
      (node (ref "C72") (pin "2") (pinfunction "2_2") (pintype "passive"))
      (node (ref "D26") (pin "2") (pintype "passive"))
      (node (ref "D27") (pin "2") (pintype "passive"))
      (node (ref "J7") (pin "13") (pinfunction "SH1_13") (pintype "passive"))
      (node (ref "J7") (pin "14") (pinfunction "SH2_14") (pintype "passive"))
    )
    (net (code "61") (name "GND") (class "Default")
      (node (ref "C65") (pin "1") (pinfunction "1_1") (pintype "passive"))
      (node (ref "C66") (pin "1") (pinfunction "1_1") (pintype "passive"))
      (node (ref "C67") (pin "1") (pinfunction "1_1") (pintype "passive"))
      (node (ref "C68") (pin "1") (pinfunction "1_1") (pintype "passive"))
      (node (ref "C69") (pin "1") (pinfunction "1_1") (pintype "passive"))
      (node (ref "C70") (pin "1") (pinfunction "1_1") (pintype "passive"))
      (node (ref "C71") (pin "1") (pinfunction "1_1") (pintype "passive"))
      (node (ref "C73") (pin "1") (pinfunction "1_1") (pintype "passive"))
      (node (ref "C74") (pin "1") (pinfunction "1_1") (pintype "passive"))
      (node (ref "C75") (pin "1") (pinfunction "1_1") (pintype "passive"))
      (node (ref "C76") (pin "2") (pinfunction "2_2") (pintype "passive"))
      (node (ref "C77") (pin "1") (pinfunction "1_1") (pintype "passive"))
      (node (ref "C78") (pin "1") (pinfunction "1_1") (pintype "passive"))
      (node (ref "C79") (pin "1") (pinfunction "1_1") (pintype "passive"))
      (node (ref "C80") (pin "1") (pinfunction "1_1") (pintype "passive"))
      (node (ref "C81") (pin "1") (pinfunction "1_1") (pintype "passive"))
      (node (ref "C82") (pin "1") (pinfunction "1_1") (pintype "passive"))
      (node (ref "C83") (pin "1") (pinfunction "1_1") (pintype "passive"))
      (node (ref "C84") (pin "1") (pinfunction "1_1") (pintype "passive"))
      (node (ref "C85") (pin "1") (pinfunction "1_1") (pintype "passive"))
      (node (ref "C86") (pin "1") (pinfunction "1_1") (pintype "passive"))
      (node (ref "C87") (pin "1") (pinfunction "1_1") (pintype "passive"))
      (node (ref "C88") (pin "1") (pinfunction "1_1") (pintype "passive"))
      (node (ref "C89") (pin "1") (pinfunction "1_1") (pintype "passive"))
      (node (ref "D28") (pin "2") (pinfunction "2_2") (pintype "passive"))
      (node (ref "D33") (pin "2") (pinfunction "2_2") (pintype "passive"))
      (node (ref "R48") (pin "1") (pinfunction "1_1") (pintype "passive"))
      (node (ref "R52") (pin "1") (pinfunction "1_1") (pintype "passive"))
      (node (ref "R59") (pin "1") (pinfunction "1_1") (pintype "passive"))
      (node (ref "R60") (pin "1") (pinfunction "1_1") (pintype "passive"))
      (node (ref "R64") (pin "1") (pinfunction "1_1") (pintype "passive"))
      (node (ref "R66") (pin "1") (pinfunction "1_1") (pintype "passive"))
      (node (ref "R68") (pin "1") (pinfunction "1_1") (pintype "passive"))
      (node (ref "R70") (pin "1") (pinfunction "1_1") (pintype "passive"))
      (node (ref "R71") (pin "1") (pinfunction "1_1") (pintype "passive"))
      (node (ref "R73") (pin "1") (pinfunction "1_1") (pintype "passive"))
      (node (ref "R74") (pin "1") (pinfunction "1_1") (pintype "passive"))
      (node (ref "R75") (pin "1") (pinfunction "1_1") (pintype "passive"))
      (node (ref "R78") (pin "1") (pinfunction "1_1") (pintype "passive"))
      (node (ref "R80") (pin "1") (pinfunction "1_1") (pintype "passive"))
      (node (ref "U20") (pin "41") (pinfunction "E_Pad_41") (pintype "passive"))
      (node (ref "Y1") (pin "2") (pinfunction "NC_2") (pintype "passive"))
      (node (ref "Y1") (pin "4") (pinfunction "NC_4") (pintype "passive"))
    )
    (net (code "62") (name "Net-(C65-Pad2)") (class "Default")
      (node (ref "C65") (pin "2") (pinfunction "2_2") (pintype "passive"))
      (node (ref "U19") (pin "1") (pinfunction "1_1") (pintype "passive"))
    )
    (net (code "63") (name "Net-(C68-Pad2)") (class "Default")
      (node (ref "C68") (pin "2") (pinfunction "2_2") (pintype "passive"))
      (node (ref "U19") (pin "4") (pinfunction "4_4") (pintype "passive"))
    )
    (net (code "64") (name "Net-(C69-Pad2)") (class "Default")
      (node (ref "C69") (pin "2") (pinfunction "2_2") (pintype "passive"))
      (node (ref "U19") (pin "7") (pinfunction "7_7") (pintype "passive"))
    )
    (net (code "65") (name "Net-(C71-Pad2)") (class "Default")
      (node (ref "C71") (pin "2") (pinfunction "2_2") (pintype "passive"))
      (node (ref "U19") (pin "10") (pinfunction "10_10") (pintype "passive"))
    )
    (net (code "66") (name "Net-(C72-Pad1)") (class "Default")
      (node (ref "C72") (pin "1") (pinfunction "1_1") (pintype "passive"))
      (node (ref "R47") (pin "2") (pinfunction "2_2") (pintype "passive"))
      (node (ref "R51") (pin "2") (pinfunction "2_2") (pintype "passive"))
      (node (ref "R56") (pin "2") (pinfunction "2_2") (pintype "passive"))
      (node (ref "R63") (pin "2") (pinfunction "2_2") (pintype "passive"))
    )
    (net (code "67") (name "Net-(D26-Pad1)") (class "Default")
      (node (ref "D26") (pin "1") (pintype "passive"))
      (node (ref "R47") (pin "1") (pinfunction "1_1") (pintype "passive"))
      (node (ref "U19") (pin "24") (pinfunction "24_24") (pintype "passive"))
    )
    (net (code "68") (name "Net-(D26-Pad3)") (class "Default")
      (node (ref "D26") (pin "3") (pintype "passive"))
      (node (ref "R51") (pin "1") (pinfunction "1_1") (pintype "passive"))
      (node (ref "U19") (pin "21") (pinfunction "21_21") (pintype "passive"))
    )
    (net (code "69") (name "Net-(D27-Pad1)") (class "Default")
      (node (ref "D27") (pin "1") (pintype "passive"))
      (node (ref "R56") (pin "1") (pinfunction "1_1") (pintype "passive"))
      (node (ref "U19") (pin "18") (pinfunction "18_18") (pintype "passive"))
    )
    (net (code "70") (name "Net-(D27-Pad3)") (class "Default")
      (node (ref "D27") (pin "3") (pintype "passive"))
      (node (ref "R63") (pin "1") (pinfunction "1_1") (pintype "passive"))
      (node (ref "U19") (pin "15") (pinfunction "15_15") (pintype "passive"))
    )
    (net (code "71") (name "Net-(J7-LED_L-)") (class "Default")
      (node (ref "J7") (pin "10") (pinfunction "LED_L-_10") (pintype "passive"))
      (node (ref "R52") (pin "2") (pinfunction "2_2") (pintype "passive"))
    )
    (net (code "72") (name "VCC3V3") (class "Default")
      (node (ref "R77") (pin "1") (pinfunction "1_1") (pintype "passive"))
      (node (ref "R82") (pin "1") (pinfunction "1_1") (pintype "passive"))
    )
    (net (code "73") (name "VCC3V3_PHY1") (class "Default")
      (node (ref "C77") (pin "2") (pinfunction "2_2") (pintype "passive"))
      (node (ref "C78") (pin "2") (pinfunction "2_2") (pintype "passive"))
      (node (ref "C79") (pin "2") (pinfunction "2_2") (pintype "passive"))
      (node (ref "C84") (pin "2") (pinfunction "2_2") (pintype "passive"))
      (node (ref "C85") (pin "2") (pinfunction "2_2") (pintype "passive"))
      (node (ref "R65") (pin "2") (pinfunction "2_2") (pintype "passive"))
      (node (ref "R67") (pin "2") (pinfunction "2_2") (pintype "passive"))
      (node (ref "R69") (pin "2") (pinfunction "2_2") (pintype "passive"))
      (node (ref "R82") (pin "2") (pinfunction "2_2") (pintype "passive"))
      (node (ref "R83") (pin "1") (pinfunction "1_1") (pintype "passive"))
      (node (ref "U20") (pin "11") (pinfunction "AVDD33_2_11") (pintype "power_in"))
      (node (ref "U20") (pin "29") (pinfunction "DVDD33_29") (pintype "power_in"))
      (node (ref "U20") (pin "40") (pinfunction "AVDD33_1_40") (pintype "power_in"))
    )
    (net (code "74") (name "VCCIO_PHY1") (class "Default")
      (node (ref "C73") (pin "2") (pinfunction "2_2") (pintype "passive"))
      (node (ref "C74") (pin "2") (pinfunction "2_2") (pintype "passive"))
      (node (ref "C75") (pin "2") (pinfunction "2_2") (pintype "passive"))
      (node (ref "R72") (pin "2") (pinfunction "2_2") (pintype "passive"))
      (node (ref "R76") (pin "2") (pinfunction "2_2") (pintype "passive"))
      (node (ref "R77") (pin "2") (pinfunction "2_2") (pintype "passive"))
      (node (ref "R79") (pin "2") (pinfunction "2_2") (pintype "passive"))
      (node (ref "R81") (pin "2") (pinfunction "2_2") (pintype "passive"))
      (node (ref "R84") (pin "2") (pinfunction "2_2") (pintype "passive"))
      (node (ref "U20") (pin "28") (pinfunction "DVDD_RG_28") (pintype "passive"))
    )
    (net (code "75") (name "VDD10_PHY1") (class "Default")
      (node (ref "C81") (pin "2") (pinfunction "2_2") (pintype "passive"))
      (node (ref "C82") (pin "2") (pinfunction "2_2") (pintype "passive"))
      (node (ref "C83") (pin "2") (pinfunction "2_2") (pintype "passive"))
      (node (ref "C86") (pin "2") (pinfunction "2_2") (pintype "passive"))
      (node (ref "C87") (pin "2") (pinfunction "2_2") (pintype "passive"))
      (node (ref "C88") (pin "2") (pinfunction "2_2") (pintype "passive"))
      (node (ref "L7") (pin "2") (pinfunction "2_2") (pintype "passive"))
      (node (ref "U20") (pin "21") (pinfunction "DVDD10_21") (pintype "power_in"))
      (node (ref "U20") (pin "3") (pinfunction "AVDD10_3_3") (pintype "power_in"))
      (node (ref "U20") (pin "38") (pinfunction "AVDD10_1_38") (pintype "power_in"))
      (node (ref "U20") (pin "8") (pinfunction "AVDD10_2_8") (pintype "power_in"))
    )
    (net (code "76") (name "unconnected-(J7-NC1-PadBO1)") (class "Default")
      (node (ref "J7") (pin "BO1") (pinfunction "NC1_BO1") (pintype "passive+no_connect"))
    )
    (net (code "77") (name "unconnected-(J7-NC2-PadBO2)") (class "Default")
      (node (ref "J7") (pin "BO2") (pinfunction "NC2_BO2") (pintype "passive+no_connect"))
    )
  )
)
